# LSR_CNTRL.net
KiCad netlist of a schematic drawn in EAGLE
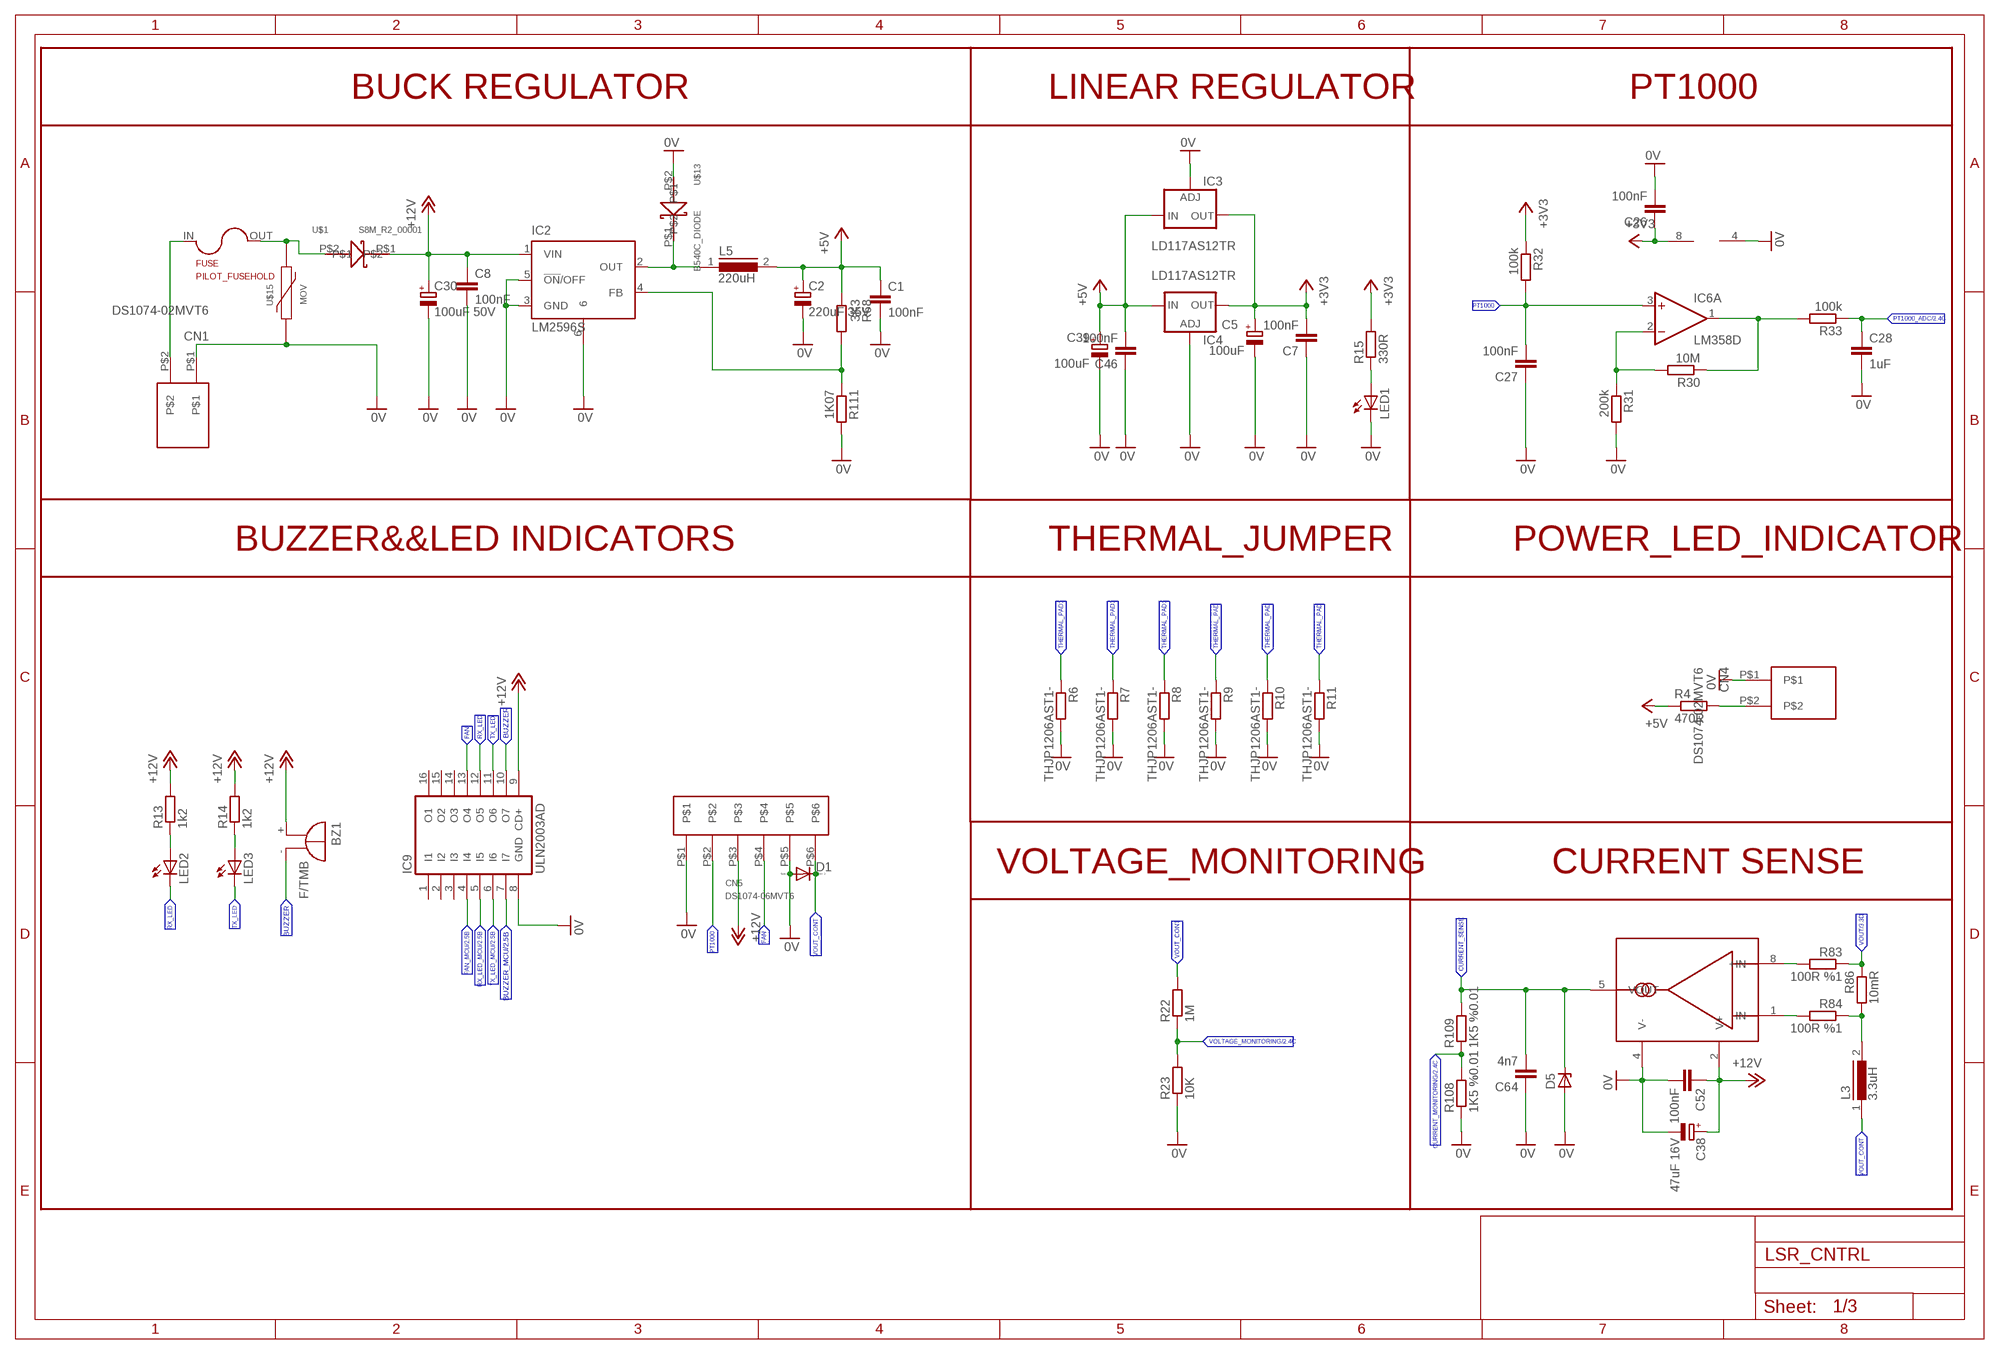
[diagram p0: schematic, sheet 1]
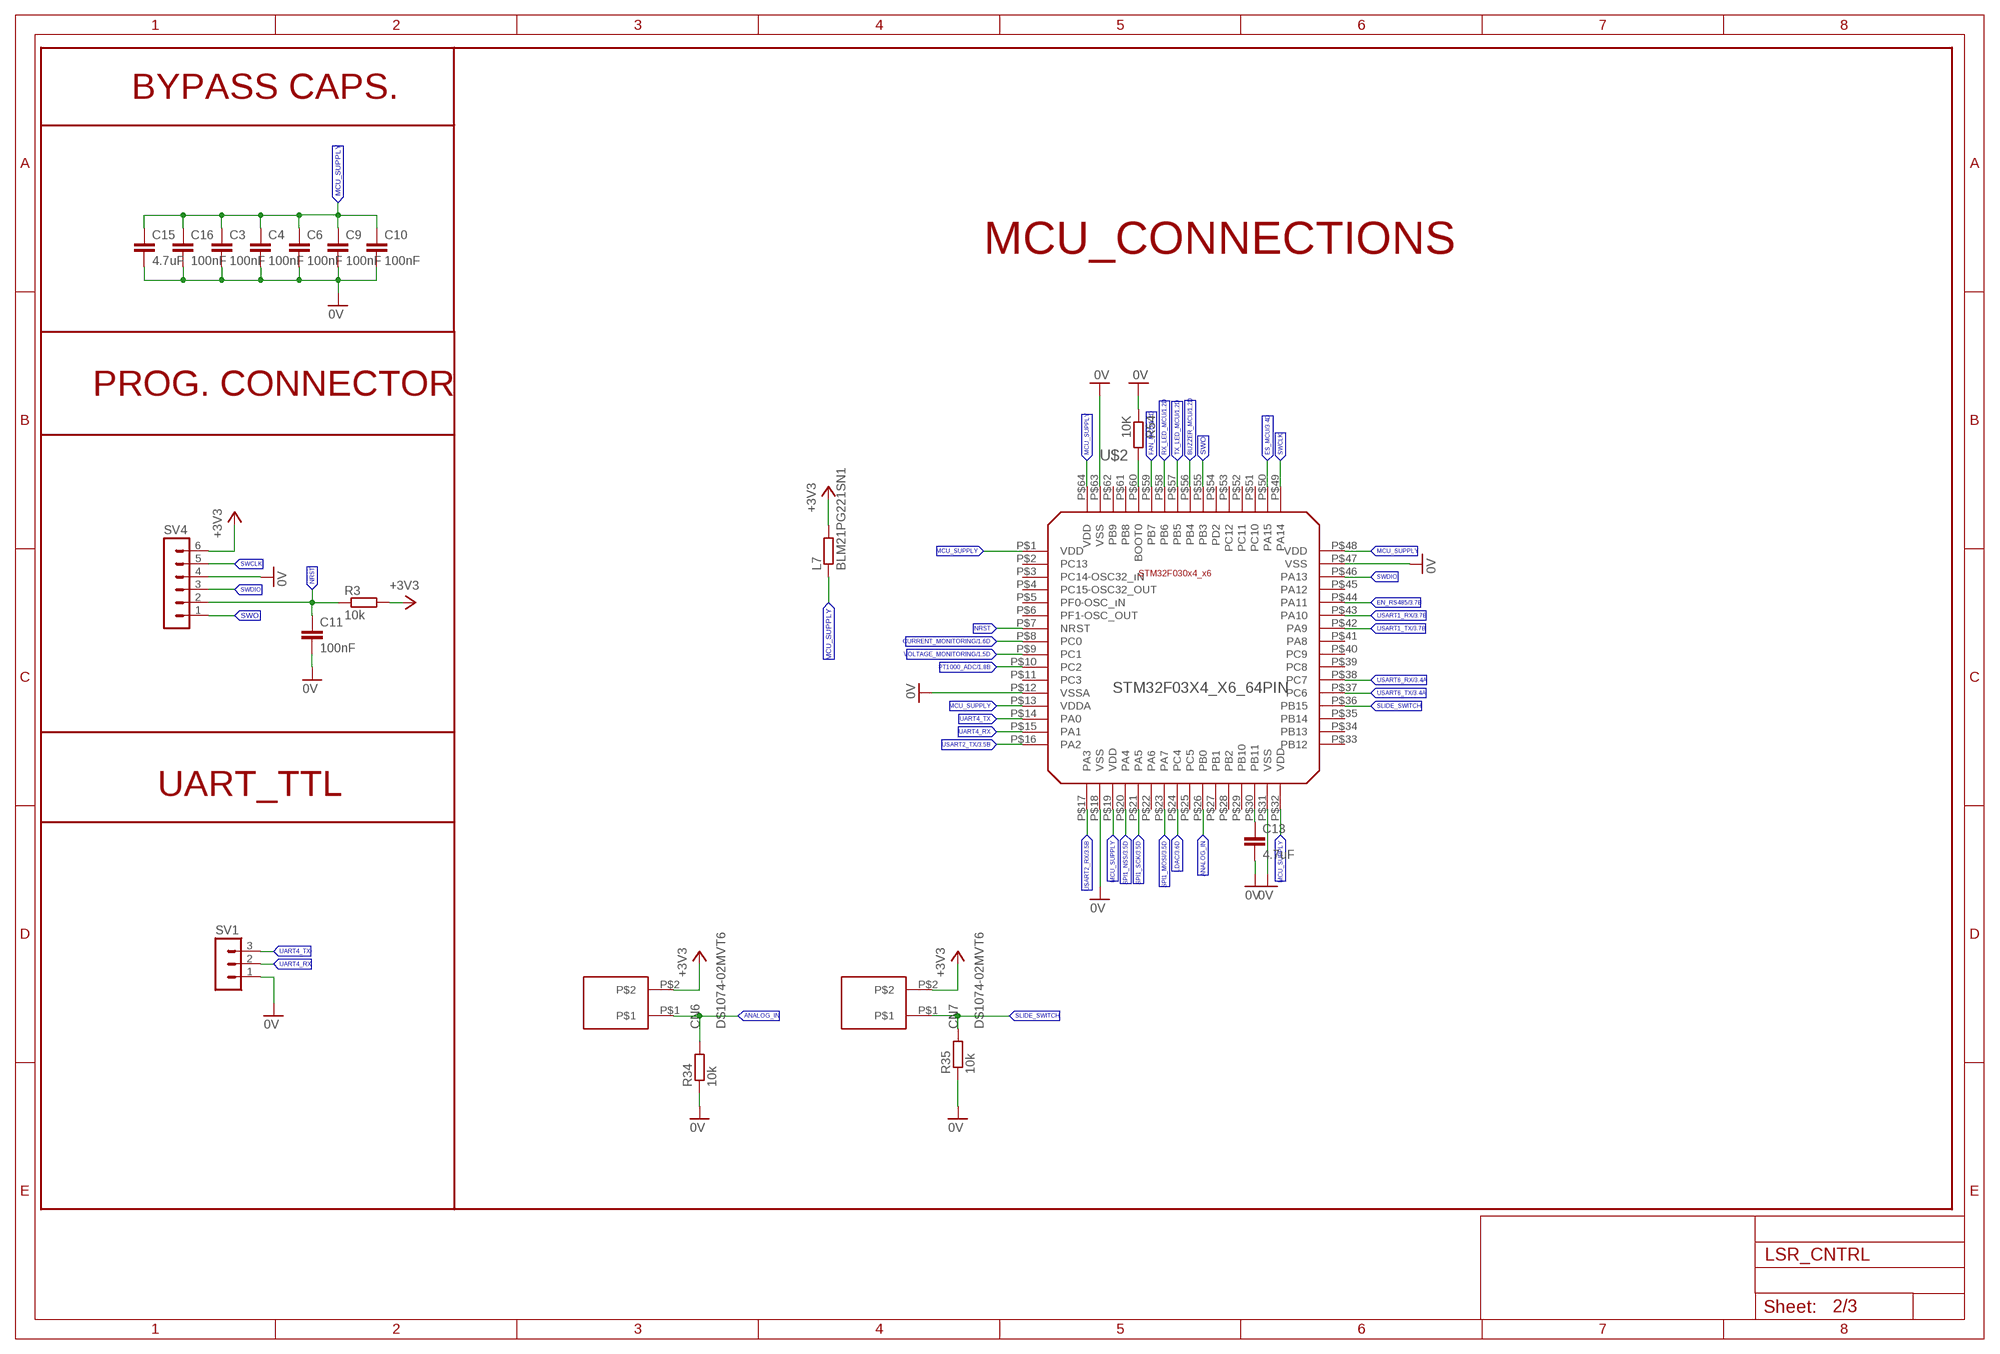
[diagram p1: schematic, sheet 2]
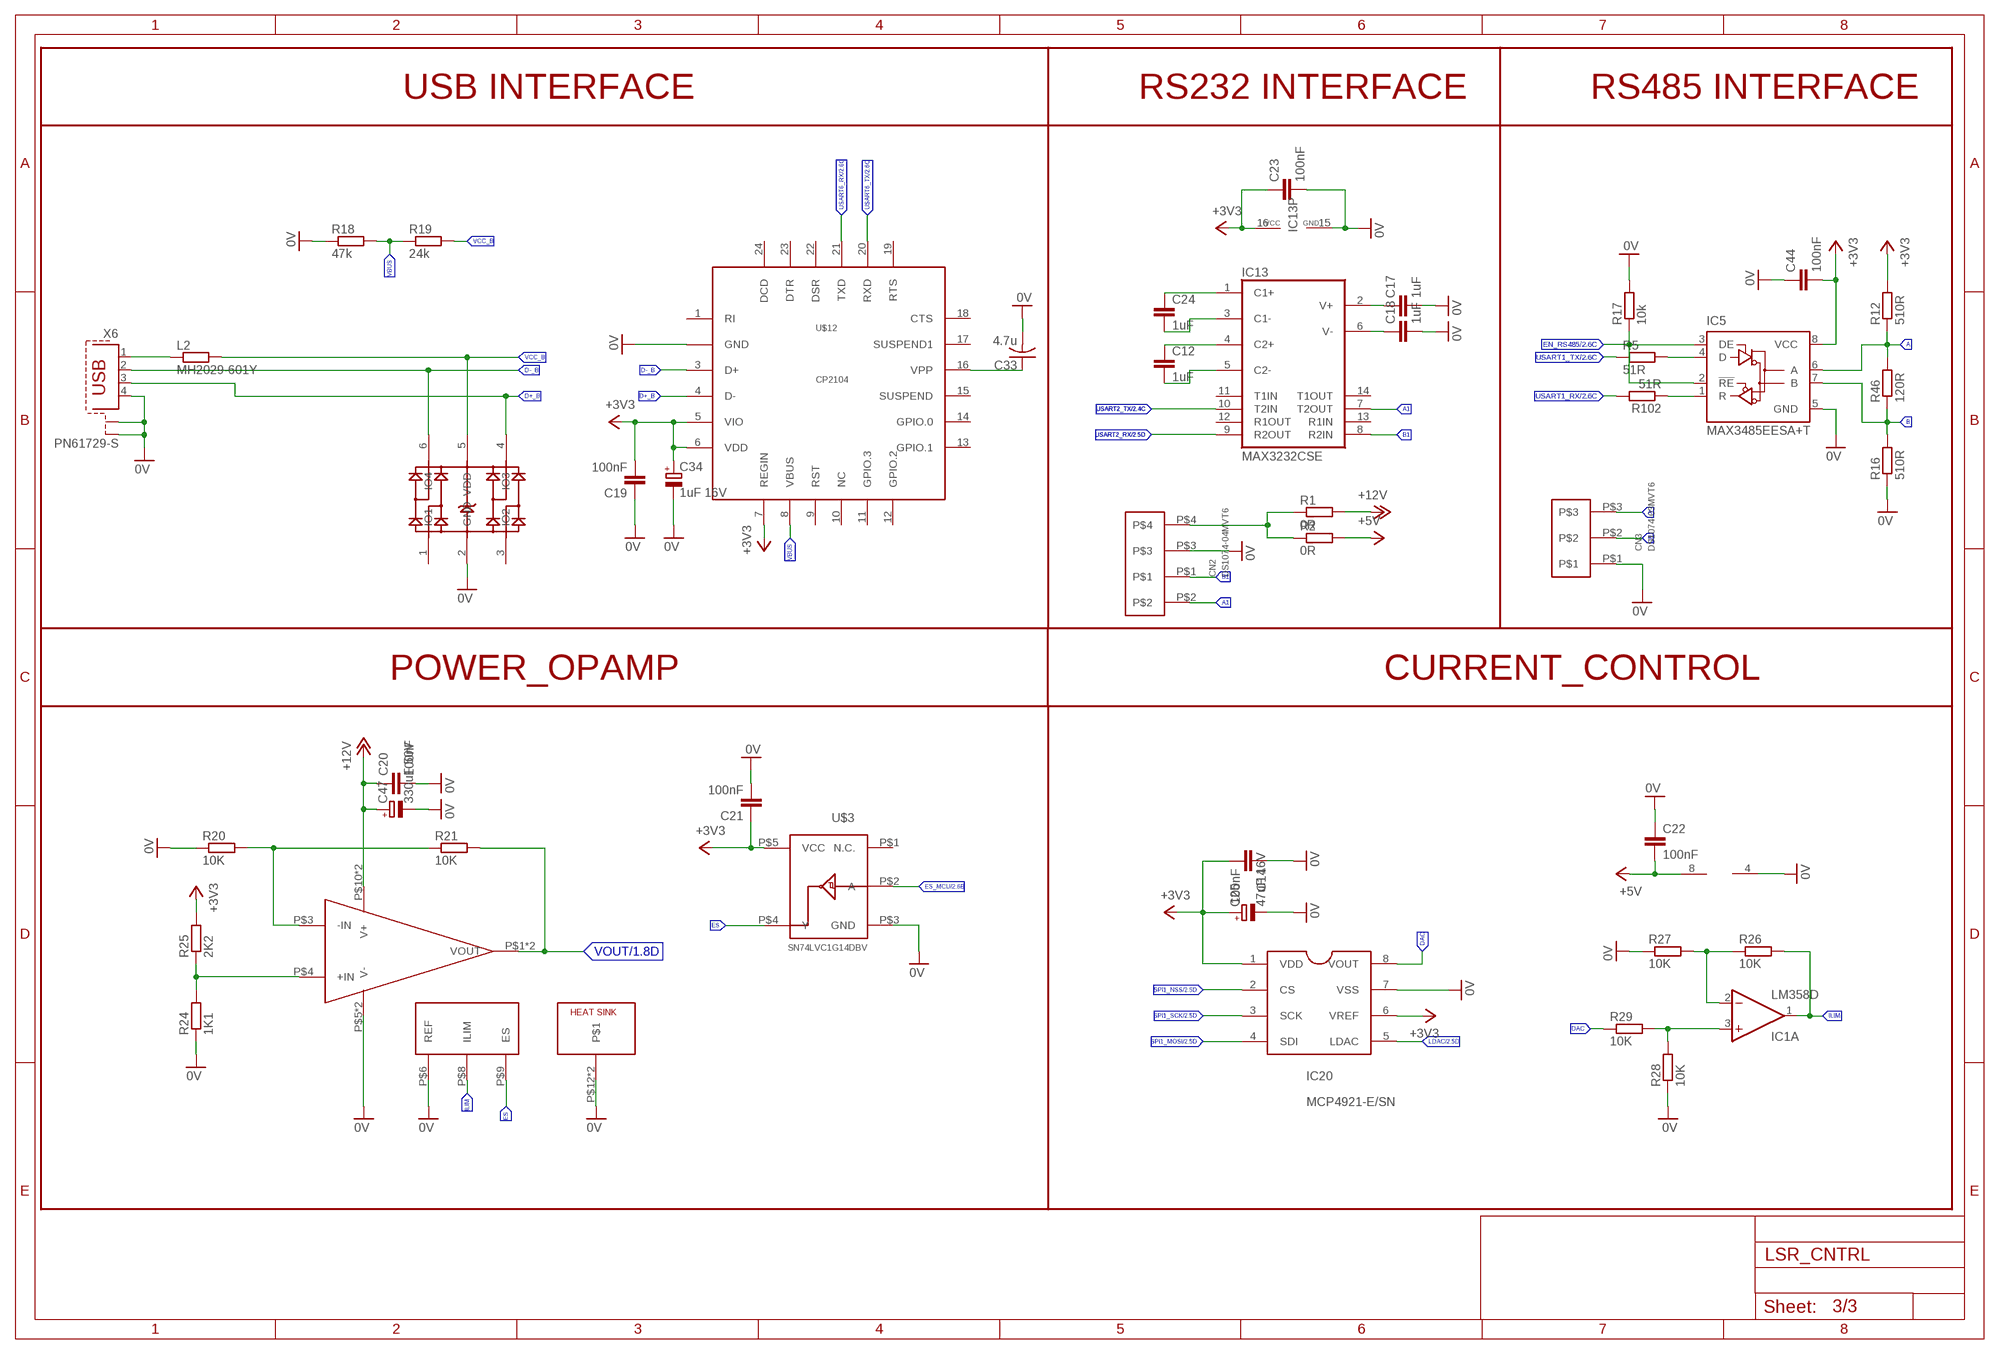
[diagram p2: schematic, sheet 3]

(export (version "E")
  (design (tool "Eeschema 10.0.6"))
  (components
    (comp (ref "C12")
      (value "1uF")
      (footprint "eagle-import:C1206")
      (libsource (lib "eagle-import") (part "C-EUC1206"))
    )
    (comp (ref "C14")
      (value "100nF")
      (footprint "eagle-import:C0603")
      (libsource (lib "eagle-import") (part "C-EUC0603"))
    )
    (comp (ref "C17")
      (value "1uF")
      (footprint "eagle-import:C1206")
      (libsource (lib "eagle-import") (part "C-EUC1206"))
    )
    (comp (ref "C18")
      (value "1uF")
      (footprint "eagle-import:C1206")
      (libsource (lib "eagle-import") (part "C-EUC1206"))
    )
    (comp (ref "C19")
      (value "100nF")
      (footprint "eagle-import:C0603")
      (libsource (lib "eagle-import") (part "C-EUC0603"))
    )
    (comp (ref "C20")
      (value "100nF")
      (footprint "eagle-import:C0603")
      (libsource (lib "eagle-import") (part "C-EUC0603"))
    )
    (comp (ref "C21")
      (value "100nF")
      (footprint "eagle-import:C0603")
      (libsource (lib "eagle-import") (part "C-EUC0603"))
    )
    (comp (ref "C22")
      (value "100nF")
      (footprint "eagle-import:C0603")
      (libsource (lib "eagle-import") (part "C-EUC0603"))
    )
    (comp (ref "C23")
      (value "100nF")
      (footprint "eagle-import:C0603")
      (libsource (lib "eagle-import") (part "C-EUC0603"))
    )
    (comp (ref "C24")
      (value "1uF")
      (footprint "eagle-import:C1206")
      (libsource (lib "eagle-import") (part "C-EUC1206"))
    )
    (comp (ref "C25")
      (value "47uF 16V")
      (footprint "eagle-import:B_3528-21R")
      (libsource (lib "eagle-import") (part "CPOL-EUB/3528-21R"))
    )
    (comp (ref "C33")
      (value "4.7u")
      (footprint "eagle-import:C0805")
      (libsource (lib "eagle-import") (part "C-USC0805"))
    )
    (comp (ref "C34")
      (value "1uF 16V")
      (footprint "eagle-import:SMC_Z")
      (libsource (lib "eagle-import") (part "CPOL-EUSMCZ"))
    )
    (comp (ref "C44")
      (value "100nF")
      (footprint "eagle-import:C0603")
      (libsource (lib "eagle-import") (part "C-EUC0603"))
    )
    (comp (ref "C47")
      (value "330uF 50V")
      (footprint "eagle-import:E5-10,5")
      (libsource (lib "eagle-import") (part "CPOL-EUE5-10.5"))
    )
    (comp (ref "CN2")
      (value "DS1074-04MVT6")
      (footprint "eagle-import:DS1074-04MVT6")
      (libsource (lib "eagle-import") (part "DS1074-04MVT6"))
    )
    (comp (ref "CN3")
      (value "DS1074-03MVT6")
      (footprint "eagle-import:DS1074-03MVT6")
      (libsource (lib "eagle-import") (part "DS1074-03MVT6"))
    )
    (comp (ref "IC1")
      (value "LM358D")
      (footprint "eagle-import:SO08")
      (libsource (lib "eagle-import") (part "LM358D"))
    )
    (comp (ref "IC5")
      (value "MAX3485EESA+T")
      (footprint "eagle-import:D_R-PDSO-G8")
      (libsource (lib "eagle-import") (part "75176AD"))
    )
    (comp (ref "IC13")
      (value "MAX3232CSE")
      (footprint "eagle-import:SO16")
      (libsource (lib "eagle-import") (part "MAX3232SEC"))
    )
    (comp (ref "IC20")
      (value "MCP4921-E/SN")
      (footprint "eagle-import:SO-08-MCP")
      (libsource (lib "eagle-import") (part "MCP4921-E/SN"))
    )
    (comp (ref "L2")
      (value "MH2029-601Y")
      (footprint "eagle-import:R0805")
      (libsource (lib "eagle-import") (part "R-EU_R0805"))
    )
    (comp (ref "OPAMP1")
      (value "OPA549MKVC")
      (footprint "eagle-import:OPA549MKVC")
      (libsource (lib "eagle-import") (part "OPA549MKVC"))
    )
    (comp (ref "R1")
      (value "0R")
      (footprint "eagle-import:R0805")
      (libsource (lib "eagle-import") (part "R-EU_R0805"))
    )
    (comp (ref "R2")
      (value "0R")
      (footprint "eagle-import:R0805")
      (libsource (lib "eagle-import") (part "R-EU_R0805"))
    )
    (comp (ref "R5")
      (value "51R")
      (footprint "eagle-import:R0603")
      (libsource (lib "eagle-import") (part "R-EU_R0603"))
    )
    (comp (ref "R12")
      (value "510R")
      (footprint "eagle-import:R0603")
      (libsource (lib "eagle-import") (part "R-EU_R0603"))
    )
    (comp (ref "R16")
      (value "510R")
      (footprint "eagle-import:R0603")
      (libsource (lib "eagle-import") (part "R-EU_R0603"))
    )
    (comp (ref "R17")
      (value "10k")
      (footprint "eagle-import:R0603")
      (libsource (lib "eagle-import") (part "R-EU_R0603"))
    )
    (comp (ref "R18")
      (value "47k")
      (footprint "eagle-import:R0805")
      (libsource (lib "eagle-import") (part "R-EU_R0805"))
    )
    (comp (ref "R19")
      (value "24k")
      (footprint "eagle-import:R0805")
      (libsource (lib "eagle-import") (part "R-EU_R0805"))
    )
    (comp (ref "R20")
      (value "10K")
      (footprint "eagle-import:R0805")
      (libsource (lib "eagle-import") (part "R-EU_R0805"))
    )
    (comp (ref "R21")
      (value "10K")
      (footprint "eagle-import:R0805")
      (libsource (lib "eagle-import") (part "R-EU_R0805"))
    )
    (comp (ref "R24")
      (value "1K1")
      (footprint "eagle-import:R0805")
      (libsource (lib "eagle-import") (part "R-EU_R0805"))
    )
    (comp (ref "R25")
      (value "2K2")
      (footprint "eagle-import:R0805")
      (libsource (lib "eagle-import") (part "R-EU_R0805"))
    )
    (comp (ref "R26")
      (value "10K")
      (footprint "eagle-import:R0805")
      (libsource (lib "eagle-import") (part "R-EU_R0805"))
    )
    (comp (ref "R27")
      (value "10K")
      (footprint "eagle-import:R0805")
      (libsource (lib "eagle-import") (part "R-EU_R0805"))
    )
    (comp (ref "R28")
      (value "10K")
      (footprint "eagle-import:R0805")
      (libsource (lib "eagle-import") (part "R-EU_R0805"))
    )
    (comp (ref "R29")
      (value "10K")
      (footprint "eagle-import:R0805")
      (libsource (lib "eagle-import") (part "R-EU_R0805"))
    )
    (comp (ref "R46")
      (value "120R")
      (footprint "eagle-import:R0603")
      (libsource (lib "eagle-import") (part "R-EU_R0603"))
    )
    (comp (ref "R102")
      (value "51R")
      (footprint "eagle-import:R0603")
      (libsource (lib "eagle-import") (part "R-EU_R0603"))
    )
    (comp (ref "TVS1")
      (value "824001")
      (footprint "eagle-import:SOT23-6")
      (libsource (lib "eagle-import") (part "824001"))
    )
    (comp (ref "U$3")
      (value "SN74LVC1G14DBV")
      (footprint "eagle-import:SOT-23-DBV")
      (libsource (lib "eagle-import") (part "SN74LVC1G14DBV"))
    )
    (comp (ref "U$12")
      (value "CP2104")
      (footprint "eagle-import:CP2104")
      (libsource (lib "eagle-import") (part "CP2104"))
    )
    (comp (ref "X6")
      (value "PN61729-S")
      (footprint "eagle-import:PN61729-S")
      (libsource (lib "eagle-import") (part "PN61729-S"))
    )
    (comp (ref "BZ1")
      (value "F/TMB")
      (footprint "eagle-import:F_TMB")
      (libsource (lib "eagle-import") (part "F/TMB"))
    )
    (comp (ref "C1")
      (value "100nF")
      (footprint "eagle-import:C0805")
      (libsource (lib "eagle-import") (part "C-EUC0805"))
    )
    (comp (ref "C2")
      (value "220uF 35V")
      (footprint "eagle-import:153CLV-0810")
      (libsource (lib "eagle-import") (part "CPOL-EU153CLV-0810"))
    )
    (comp (ref "C5")
      (value "100uF")
      (footprint "eagle-import:153CLV-0605")
      (libsource (lib "eagle-import") (part "CPOL-EU153CLV-0605"))
    )
    (comp (ref "C7")
      (value "100nF")
      (footprint "eagle-import:C0603")
      (libsource (lib "eagle-import") (part "C-EUC0603"))
    )
    (comp (ref "C8")
      (value "100nF")
      (footprint "eagle-import:C0805")
      (libsource (lib "eagle-import") (part "C-EUC0805"))
    )
    (comp (ref "C26")
      (value "100nF")
      (footprint "eagle-import:C0603")
      (libsource (lib "eagle-import") (part "C-EUC0603"))
    )
    (comp (ref "C27")
      (value "100nF")
      (footprint "eagle-import:C0603")
      (libsource (lib "eagle-import") (part "C-EUC0603"))
    )
    (comp (ref "C28")
      (value "1uF")
      (footprint "eagle-import:C1206")
      (libsource (lib "eagle-import") (part "C-EUC1206"))
    )
    (comp (ref "C30")
      (value "100uF 50V")
      (footprint "eagle-import:153CLV-0810")
      (libsource (lib "eagle-import") (part "CPOL-EU153CLV-0810"))
    )
    (comp (ref "C38")
      (value "47uF 16V")
      (footprint "eagle-import:B_3528-21R")
      (libsource (lib "eagle-import") (part "CPOL-EUB/3528-21R"))
    )
    (comp (ref "C39")
      (value "100uF")
      (footprint "eagle-import:153CLV-0605")
      (libsource (lib "eagle-import") (part "CPOL-EU153CLV-0605"))
    )
    (comp (ref "C46")
      (value "100nF")
      (footprint "eagle-import:C0603")
      (libsource (lib "eagle-import") (part "C-EUC0603"))
    )
    (comp (ref "C52")
      (value "100nF")
      (footprint "eagle-import:C0805")
      (libsource (lib "eagle-import") (part "C-EUC0805"))
    )
    (comp (ref "C64")
      (value "4n7")
      (footprint "eagle-import:C0805")
      (libsource (lib "eagle-import") (part "C-EUC0805"))
    )
    (comp (ref "CN1")
      (value "DS1074-02MVT6")
      (footprint "eagle-import:DS1074-02MVT6")
      (libsource (lib "eagle-import") (part "DS1074-02MVT6"))
    )
    (comp (ref "CN4")
      (value "DS1074-02MVT6")
      (footprint "eagle-import:DS1074-02MVT6")
      (libsource (lib "eagle-import") (part "DS1074-02MVT6"))
    )
    (comp (ref "CN5")
      (value "DS1074-06MVT6")
      (footprint "eagle-import:DS1074-06MVT6")
      (libsource (lib "eagle-import") (part "DS1074-06MVT6"))
    )
    (comp (ref "D1")
      (value "DIODE-SMB")
      (footprint "eagle-import:SMB")
      (libsource (lib "eagle-import") (part "DIODE-SMB"))
    )
    (comp (ref "D5")
      (value "ZENER-DIODESOD80C")
      (footprint "eagle-import:SOD80C")
      (libsource (lib "eagle-import") (part "ZENER-DIODESOD80C"))
    )
    (comp (ref "FUSE")
      (value "PILOT_FUSEHOLD")
      (footprint "eagle-import:RTM_FUSEHOLD")
      (libsource (lib "eagle-import") (part "RTM_FUSEHOLD"))
    )
    (comp (ref "IC2")
      (value "LM2596S")
      (footprint "eagle-import:TO263-5")
      (fields (field (name "MF") "NATIONAL SEMICONDUCTOR") (field (name "MPN") "LM2596S-ADJ/NOPB"))
      (libsource (lib "eagle-import") (part "LM2596S"))
    )
    (comp (ref "IC3")
      (value "LD117AS12TR")
      (footprint "eagle-import:SOT223")
      (libsource (lib "eagle-import") (part "LD117A?S12TR"))
    )
    (comp (ref "IC4")
      (value "LD117AS12TR")
      (footprint "eagle-import:SOT223")
      (libsource (lib "eagle-import") (part "LD117A?S12TR"))
    )
    (comp (ref "IC6")
      (value "LM358D")
      (footprint "eagle-import:SO08")
      (libsource (lib "eagle-import") (part "LM358D"))
    )
    (comp (ref "IC9")
      (value "ULN2003AD")
      (footprint "eagle-import:SO16")
      (libsource (lib "eagle-import") (part "ULN2003AD"))
    )
    (comp (ref "L3")
      (value "3.3uH")
      (footprint "eagle-import:DR127")
      (libsource (lib "eagle-import") (part "DR127"))
    )
    (comp (ref "L5")
      (value "220uH")
      (footprint "eagle-import:DR125")
      (libsource (lib "eagle-import") (part "DR125"))
    )
    (comp (ref "LED1")
      (value "LEDCHIPLED_0805")
      (footprint "eagle-import:CHIPLED_0805")
      (libsource (lib "eagle-import") (part "LEDCHIPLED_0805"))
    )
    (comp (ref "LED2")
      (value "LEDCHIPLED_0805")
      (footprint "eagle-import:CHIPLED_0805")
      (libsource (lib "eagle-import") (part "LEDCHIPLED_0805"))
    )
    (comp (ref "LED3")
      (value "LEDCHIPLED_0805")
      (footprint "eagle-import:CHIPLED_0805")
      (libsource (lib "eagle-import") (part "LEDCHIPLED_0805"))
    )
    (comp (ref "R4")
      (value "470R")
      (footprint "eagle-import:M0805")
      (libsource (lib "eagle-import") (part "R-EU_M0805"))
    )
    (comp (ref "R6")
      (value "THJP1206AST1-")
      (footprint "eagle-import:M0805")
      (libsource (lib "eagle-import") (part "R-EU_M0805"))
    )
    (comp (ref "R7")
      (value "THJP1206AST1-")
      (footprint "eagle-import:M0805")
      (libsource (lib "eagle-import") (part "R-EU_M0805"))
    )
    (comp (ref "R8")
      (value "THJP1206AST1-")
      (footprint "eagle-import:M0805")
      (libsource (lib "eagle-import") (part "R-EU_M0805"))
    )
    (comp (ref "R9")
      (value "THJP1206AST1-")
      (footprint "eagle-import:M0805")
      (libsource (lib "eagle-import") (part "R-EU_M0805"))
    )
    (comp (ref "R10")
      (value "THJP1206AST1-")
      (footprint "eagle-import:M0805")
      (libsource (lib "eagle-import") (part "R-EU_M0805"))
    )
    (comp (ref "R11")
      (value "THJP1206AST1-")
      (footprint "eagle-import:M0805")
      (libsource (lib "eagle-import") (part "R-EU_M0805"))
    )
    (comp (ref "R13")
      (value "1k2")
      (footprint "eagle-import:R0603")
      (libsource (lib "eagle-import") (part "R-EU_R0603"))
    )
    (comp (ref "R14")
      (value "1k2")
      (footprint "eagle-import:R0603")
      (libsource (lib "eagle-import") (part "R-EU_R0603"))
    )
    (comp (ref "R15")
      (value "330R")
      (footprint "eagle-import:R0603")
      (libsource (lib "eagle-import") (part "R-EU_R0603"))
    )
    (comp (ref "R22")
      (value "1M")
      (footprint "eagle-import:R0603")
      (libsource (lib "eagle-import") (part "R-EU_R0603"))
    )
    (comp (ref "R23")
      (value "10K")
      (footprint "eagle-import:R0603")
      (libsource (lib "eagle-import") (part "R-EU_R0603"))
    )
    (comp (ref "R30")
      (value "10M")
      (footprint "eagle-import:R0603")
      (libsource (lib "eagle-import") (part "R-EU_R0603"))
    )
    (comp (ref "R31")
      (value "200k")
      (footprint "eagle-import:R0603")
      (libsource (lib "eagle-import") (part "R-EU_R0603"))
    )
    (comp (ref "R32")
      (value "100k")
      (footprint "eagle-import:R0603")
      (libsource (lib "eagle-import") (part "R-EU_R0603"))
    )
    (comp (ref "R33")
      (value "100k")
      (footprint "eagle-import:R0603")
      (libsource (lib "eagle-import") (part "R-EU_R0603"))
    )
    (comp (ref "R68")
      (value "3K3")
      (footprint "eagle-import:M0805")
      (libsource (lib "eagle-import") (part "R-EU_M0805"))
    )
    (comp (ref "R83")
      (value "100R %1")
      (footprint "eagle-import:R0805")
      (libsource (lib "eagle-import") (part "R-EU_R0805"))
    )
    (comp (ref "R84")
      (value "100R %1")
      (footprint "eagle-import:R0805")
      (libsource (lib "eagle-import") (part "R-EU_R0805"))
    )
    (comp (ref "R86")
      (value "10mR")
      (footprint "eagle-import:R2512")
      (libsource (lib "eagle-import") (part "R-EU_R2512"))
    )
    (comp (ref "R108")
      (value "1K5 %0.01")
      (footprint "eagle-import:R0603")
      (libsource (lib "eagle-import") (part "R-EU_R0603"))
    )
    (comp (ref "R109")
      (value "1K5 %0.01")
      (footprint "eagle-import:R0603")
      (libsource (lib "eagle-import") (part "R-EU_R0603"))
    )
    (comp (ref "R111")
      (value "1K07")
      (footprint "eagle-import:M0805")
      (libsource (lib "eagle-import") (part "R-EU_M0805"))
    )
    (comp (ref "U$1")
      (value "S8M_R2_00001")
      (footprint "eagle-import:SMC")
      (libsource (lib "eagle-import") (part "B540C_DIODE"))
    )
    (comp (ref "U$5")
      (value "LT6105")
      (footprint "eagle-import:MSOP-8")
      (libsource (lib "eagle-import") (part "LT6105"))
    )
    (comp (ref "U$13")
      (value "B540C_DIODE")
      (footprint "eagle-import:SMC")
      (libsource (lib "eagle-import") (part "B540C_DIODE"))
    )
    (comp (ref "U$15")
      (value "MOV-10D201K")
      (footprint "eagle-import:MOV-10D201K")
      (libsource (lib "eagle-import") (part "MOV-10D201K"))
    )
    (comp (ref "C3")
      (value "100nF")
      (footprint "eagle-import:C0603")
      (libsource (lib "eagle-import") (part "C-EUC0603"))
    )
    (comp (ref "C4")
      (value "100nF")
      (footprint "eagle-import:C0603")
      (libsource (lib "eagle-import") (part "C-EUC0603"))
    )
    (comp (ref "C6")
      (value "100nF")
      (footprint "eagle-import:C0603")
      (libsource (lib "eagle-import") (part "C-EUC0603"))
    )
    (comp (ref "C9")
      (value "100nF")
      (footprint "eagle-import:C0603")
      (libsource (lib "eagle-import") (part "C-EUC0603"))
    )
    (comp (ref "C10")
      (value "100nF")
      (footprint "eagle-import:C0603")
      (libsource (lib "eagle-import") (part "C-EUC0603"))
    )
    (comp (ref "C11")
      (value "100nF")
      (footprint "eagle-import:C0603")
      (libsource (lib "eagle-import") (part "C-EUC0603"))
    )
    (comp (ref "C13")
      (value "4.7uF")
      (footprint "eagle-import:C0805")
      (libsource (lib "eagle-import") (part "C-EUC0805"))
    )
    (comp (ref "C15")
      (value "4.7uF")
      (footprint "eagle-import:C0805")
      (libsource (lib "eagle-import") (part "C-EUC0805"))
    )
    (comp (ref "C16")
      (value "100nF")
      (footprint "eagle-import:C0603")
      (libsource (lib "eagle-import") (part "C-EUC0603"))
    )
    (comp (ref "CN6")
      (value "DS1074-02MVT6")
      (footprint "eagle-import:DS1074-02MVT6")
      (libsource (lib "eagle-import") (part "DS1074-02MVT6"))
    )
    (comp (ref "CN7")
      (value "DS1074-02MVT6")
      (footprint "eagle-import:DS1074-02MVT6")
      (libsource (lib "eagle-import") (part "DS1074-02MVT6"))
    )
    (comp (ref "L7")
      (value "BLM21PG221SN1")
      (footprint "eagle-import:R0805")
      (libsource (lib "eagle-import") (part "R-EU_R0805"))
    )
    (comp (ref "R3")
      (value "10k")
      (footprint "eagle-import:R0603")
      (libsource (lib "eagle-import") (part "R-EU_R0603"))
    )
    (comp (ref "R34")
      (value "10k")
      (footprint "eagle-import:R0603")
      (libsource (lib "eagle-import") (part "R-EU_R0603"))
    )
    (comp (ref "R35")
      (value "10k")
      (footprint "eagle-import:R0603")
      (libsource (lib "eagle-import") (part "R-EU_R0603"))
    )
    (comp (ref "R54")
      (value "10K")
      (footprint "eagle-import:R0603")
      (libsource (lib "eagle-import") (part "R-EU_R0603"))
    )
    (comp (ref "SV1")
      (value "MA03-1")
      (footprint "eagle-import:MA03-1")
      (libsource (lib "eagle-import") (part "MA03-1"))
    )
    (comp (ref "SV4")
      (value "MA06-1")
      (footprint "eagle-import:MA06-1")
      (libsource (lib "eagle-import") (part "MA06-1"))
    )
    (comp (ref "U$2")
      (value "STM32F03X4_X6_64PIN")
      (footprint "eagle-import:LQFP64")
      (libsource (lib "eagle-import") (part "STM32F03X4_X6_64PIN"))
    )
  )
  (nets
    (net (code "1") (name "+3V3") (class "Default")
      (node (ref "C14") (pin "2") (pinfunction "2_2") (pintype "passive"))
      (node (ref "C19") (pin "2") (pinfunction "2_2") (pintype "passive"))
      (node (ref "C21") (pin "1") (pinfunction "1_1") (pintype "passive"))
      (node (ref "C23") (pin "1") (pinfunction "1_1") (pintype "passive"))
      (node (ref "C25") (pin "+") (pinfunction "+_+") (pintype "passive"))
      (node (ref "C26") (pin "1") (pinfunction "1_1") (pintype "passive"))
      (node (ref "C34") (pin "+") (pinfunction "+_+") (pintype "passive"))
      (node (ref "C44") (pin "2") (pinfunction "2_2") (pintype "passive"))
      (node (ref "C5") (pin "+") (pinfunction "+_+") (pintype "passive"))
      (node (ref "C7") (pin "2") (pinfunction "2_2") (pintype "passive"))
      (node (ref "CN6") (pin "P$2") (pinfunction "P$2_P$2") (pintype "bidirectional"))
      (node (ref "CN7") (pin "P$2") (pinfunction "P$2_P$2") (pintype "bidirectional"))
      (node (ref "IC13") (pin "16") (pinfunction "VCC_16") (pintype "power_in"))
      (node (ref "IC20") (pin "1") (pinfunction "VDD_1") (pintype "bidirectional"))
      (node (ref "IC20") (pin "6") (pinfunction "VREF_6") (pintype "bidirectional"))
      (node (ref "IC3") (pin "4") (pinfunction "OUT_4") (pintype "passive"))
      (node (ref "IC4") (pin "4") (pinfunction "OUT_4") (pintype "passive"))
      (node (ref "IC5") (pin "8") (pinfunction "VCC_8") (pintype "power_in"))
      (node (ref "IC6") (pin "8") (pinfunction "V+_8") (pintype "power_in"))
      (node (ref "L7") (pin "2") (pinfunction "2_2") (pintype "passive"))
      (node (ref "R12") (pin "2") (pinfunction "2_2") (pintype "passive"))
      (node (ref "R15") (pin "2") (pinfunction "2_2") (pintype "passive"))
      (node (ref "R25") (pin "2") (pinfunction "2_2") (pintype "passive"))
      (node (ref "R3") (pin "2") (pinfunction "2_2") (pintype "passive"))
      (node (ref "R32") (pin "1") (pinfunction "1_1") (pintype "passive"))
      (node (ref "SV4") (pin "6") (pinfunction "6_6") (pintype "passive"))
      (node (ref "U$12") (pin "5") (pinfunction "VIO_5") (pintype "bidirectional"))
      (node (ref "U$12") (pin "6") (pinfunction "VDD_6") (pintype "bidirectional"))
      (node (ref "U$12") (pin "7") (pinfunction "REGIN_7") (pintype "bidirectional"))
      (node (ref "U$3") (pin "P$5") (pinfunction "VCC_P$5") (pintype "bidirectional"))
    )
    (net (code "2") (name "+5V") (class "Default")
      (node (ref "C1") (pin "1") (pinfunction "1_1") (pintype "passive"))
      (node (ref "C2") (pin "+") (pinfunction "+_+") (pintype "passive"))
      (node (ref "C22") (pin "2") (pinfunction "2_2") (pintype "passive"))
      (node (ref "C39") (pin "+") (pinfunction "+_+") (pintype "passive"))
      (node (ref "C46") (pin "2") (pinfunction "2_2") (pintype "passive"))
      (node (ref "IC1") (pin "8") (pinfunction "V+_8") (pintype "power_in"))
      (node (ref "IC3") (pin "3") (pinfunction "IN_3") (pintype "input"))
      (node (ref "IC4") (pin "3") (pinfunction "IN_3") (pintype "input"))
      (node (ref "L5") (pin "2") (pinfunction "2_2") (pintype "passive"))
      (node (ref "R2") (pin "2") (pinfunction "2_2") (pintype "passive"))
      (node (ref "R4") (pin "1") (pinfunction "1_1") (pintype "passive"))
      (node (ref "R68") (pin "1") (pinfunction "1_1") (pintype "passive"))
    )
    (net (code "3") (name "+12V") (class "Default")
      (node (ref "BZ1") (pin "+") (pinfunction "+_+") (pintype "passive"))
      (node (ref "C20") (pin "1") (pinfunction "1_1") (pintype "passive"))
      (node (ref "C30") (pin "+") (pinfunction "+_+") (pintype "passive"))
      (node (ref "C38") (pin "+") (pinfunction "+_+") (pintype "passive"))
      (node (ref "C47") (pin "+") (pinfunction "+_+") (pintype "passive"))
      (node (ref "C52") (pin "1") (pinfunction "1_1") (pintype "passive"))
      (node (ref "C8") (pin "1") (pinfunction "1_1") (pintype "passive"))
      (node (ref "CN5") (pin "P$3") (pinfunction "P$3_P$3") (pintype "bidirectional"))
      (node (ref "IC2") (pin "1") (pinfunction "VIN_1") (pintype "input"))
      (node (ref "IC9") (pin "9") (pinfunction "CD+_9") (pintype "passive"))
      (node (ref "OPAMP1") (pin "P$10") (pinfunction "V+_P$10") (pintype "bidirectional"))
      (node (ref "OPAMP1") (pin "P$11") (pinfunction "V+_P$11") (pintype "bidirectional"))
      (node (ref "R1") (pin "2") (pinfunction "2_2") (pintype "passive"))
      (node (ref "R13") (pin "2") (pinfunction "2_2") (pintype "passive"))
      (node (ref "R14") (pin "2") (pinfunction "2_2") (pintype "passive"))
      (node (ref "U$1") (pin "P$1") (pinfunction "P$1_P$1") (pintype "bidirectional"))
      (node (ref "U$5") (pin "2") (pinfunction "V+_2") (pintype "bidirectional"))
    )
    (net (code "4") (name "0V") (class "Default")
      (node (ref "C1") (pin "2") (pinfunction "2_2") (pintype "passive"))
      (node (ref "C10") (pin "2") (pinfunction "2_2") (pintype "passive"))
      (node (ref "C11") (pin "2") (pinfunction "2_2") (pintype "passive"))
      (node (ref "C13") (pin "2") (pinfunction "2_2") (pintype "passive"))
      (node (ref "C14") (pin "1") (pinfunction "1_1") (pintype "passive"))
      (node (ref "C15") (pin "2") (pinfunction "2_2") (pintype "passive"))
      (node (ref "C16") (pin "2") (pinfunction "2_2") (pintype "passive"))
      (node (ref "C17") (pin "2") (pinfunction "2_2") (pintype "passive"))
      (node (ref "C18") (pin "2") (pinfunction "2_2") (pintype "passive"))
      (node (ref "C19") (pin "1") (pinfunction "1_1") (pintype "passive"))
      (node (ref "C2") (pin "-") (pinfunction "-_-") (pintype "passive"))
      (node (ref "C20") (pin "2") (pinfunction "2_2") (pintype "passive"))
      (node (ref "C21") (pin "2") (pinfunction "2_2") (pintype "passive"))
      (node (ref "C22") (pin "1") (pinfunction "1_1") (pintype "passive"))
      (node (ref "C23") (pin "2") (pinfunction "2_2") (pintype "passive"))
      (node (ref "C25") (pin "-") (pinfunction "-_-") (pintype "passive"))
      (node (ref "C26") (pin "2") (pinfunction "2_2") (pintype "passive"))
      (node (ref "C27") (pin "1") (pinfunction "1_1") (pintype "passive"))
      (node (ref "C28") (pin "2") (pinfunction "2_2") (pintype "passive"))
      (node (ref "C3") (pin "2") (pinfunction "2_2") (pintype "passive"))
      (node (ref "C30") (pin "-") (pinfunction "-_-") (pintype "passive"))
      (node (ref "C33") (pin "2") (pinfunction "2_2") (pintype "passive"))
      (node (ref "C34") (pin "-") (pinfunction "-_-") (pintype "passive"))
      (node (ref "C38") (pin "-") (pinfunction "-_-") (pintype "passive"))
      (node (ref "C39") (pin "-") (pinfunction "-_-") (pintype "passive"))
      (node (ref "C4") (pin "2") (pinfunction "2_2") (pintype "passive"))
      (node (ref "C44") (pin "1") (pinfunction "1_1") (pintype "passive"))
      (node (ref "C46") (pin "1") (pinfunction "1_1") (pintype "passive"))
      (node (ref "C47") (pin "-") (pinfunction "-_-") (pintype "passive"))
      (node (ref "C5") (pin "-") (pinfunction "-_-") (pintype "passive"))
      (node (ref "C52") (pin "2") (pinfunction "2_2") (pintype "passive"))
      (node (ref "C6") (pin "2") (pinfunction "2_2") (pintype "passive"))
      (node (ref "C64") (pin "1") (pinfunction "1_1") (pintype "passive"))
      (node (ref "C7") (pin "1") (pinfunction "1_1") (pintype "passive"))
      (node (ref "C8") (pin "2") (pinfunction "2_2") (pintype "passive"))
      (node (ref "C9") (pin "2") (pinfunction "2_2") (pintype "passive"))
      (node (ref "CN1") (pin "P$1") (pinfunction "P$1_P$1") (pintype "bidirectional"))
      (node (ref "CN2") (pin "P$3") (pinfunction "P$3_P$3") (pintype "bidirectional"))
      (node (ref "CN3") (pin "P$1") (pinfunction "P$1_P$1") (pintype "bidirectional"))
      (node (ref "CN4") (pin "P$1") (pinfunction "P$1_P$1") (pintype "bidirectional"))
      (node (ref "CN5") (pin "P$1") (pinfunction "P$1_P$1") (pintype "bidirectional"))
      (node (ref "CN5") (pin "P$5") (pinfunction "P$5_P$5") (pintype "bidirectional"))
      (node (ref "D1") (pin "A") (pinfunction "A_A") (pintype "passive"))
      (node (ref "D5") (pin "A") (pinfunction "A_A") (pintype "passive"))
      (node (ref "IC1") (pin "4") (pinfunction "V-_4") (pintype "power_in"))
      (node (ref "IC13") (pin "15") (pinfunction "GND_15") (pintype "power_in"))
      (node (ref "IC2") (pin "3") (pinfunction "GND_3") (pintype "power_in"))
      (node (ref "IC2") (pin "5") (pinfunction "~{ON}/OFF_5") (pintype "input"))
      (node (ref "IC2") (pin "6") (pinfunction "6_6") (pintype "bidirectional"))
      (node (ref "IC20") (pin "7") (pinfunction "VSS_7") (pintype "bidirectional"))
      (node (ref "IC3") (pin "1") (pinfunction "ADJ_1") (pintype "input"))
      (node (ref "IC4") (pin "1") (pinfunction "ADJ_1") (pintype "input"))
      (node (ref "IC5") (pin "5") (pinfunction "GND_5") (pintype "power_in"))
      (node (ref "IC6") (pin "4") (pinfunction "V-_4") (pintype "power_in"))
      (node (ref "IC9") (pin "8") (pinfunction "GND_8") (pintype "power_in"))
      (node (ref "LED1") (pin "C") (pinfunction "C_C") (pintype "passive"))
      (node (ref "OPAMP1") (pin "P$12") (pinfunction "P$1_P$12") (pintype "bidirectional"))
      (node (ref "OPAMP1") (pin "P$13") (pinfunction "P$1_P$13") (pintype "bidirectional"))
      (node (ref "OPAMP1") (pin "P$5") (pinfunction "V-_P$5") (pintype "bidirectional"))
      (node (ref "OPAMP1") (pin "P$6") (pinfunction "REF_P$6") (pintype "bidirectional"))
      (node (ref "OPAMP1") (pin "P$7") (pinfunction "V-_P$7") (pintype "bidirectional"))
      (node (ref "R10") (pin "2") (pinfunction "2_2") (pintype "passive"))
      (node (ref "R108") (pin "1") (pinfunction "1_1") (pintype "passive"))
      (node (ref "R11") (pin "2") (pinfunction "2_2") (pintype "passive"))
      (node (ref "R111") (pin "2") (pinfunction "2_2") (pintype "passive"))
      (node (ref "R16") (pin "1") (pinfunction "1_1") (pintype "passive"))
      (node (ref "R17") (pin "2") (pinfunction "2_2") (pintype "passive"))
      (node (ref "R18") (pin "1") (pinfunction "1_1") (pintype "passive"))
      (node (ref "R20") (pin "1") (pinfunction "1_1") (pintype "passive"))
      (node (ref "R23") (pin "1") (pinfunction "1_1") (pintype "passive"))
      (node (ref "R24") (pin "1") (pinfunction "1_1") (pintype "passive"))
      (node (ref "R27") (pin "1") (pinfunction "1_1") (pintype "passive"))
      (node (ref "R28") (pin "1") (pinfunction "1_1") (pintype "passive"))
      (node (ref "R31") (pin "2") (pinfunction "2_2") (pintype "passive"))
      (node (ref "R34") (pin "1") (pinfunction "1_1") (pintype "passive"))
      (node (ref "R35") (pin "1") (pinfunction "1_1") (pintype "passive"))
      (node (ref "R54") (pin "1") (pinfunction "1_1") (pintype "passive"))
      (node (ref "R6") (pin "2") (pinfunction "2_2") (pintype "passive"))
      (node (ref "R7") (pin "2") (pinfunction "2_2") (pintype "passive"))
      (node (ref "R8") (pin "2") (pinfunction "2_2") (pintype "passive"))
      (node (ref "R9") (pin "2") (pinfunction "2_2") (pintype "passive"))
      (node (ref "SV1") (pin "1") (pinfunction "1_1") (pintype "passive"))
      (node (ref "SV4") (pin "4") (pinfunction "4_4") (pintype "passive"))
      (node (ref "TVS1") (pin "2") (pinfunction "GND_2") (pintype "bidirectional"))
      (node (ref "U$12") (pin "2") (pinfunction "GND_2") (pintype "bidirectional"))
      (node (ref "U$12") (pin "GND1") (pinfunction "GND_GND1") (pintype "bidirectional"))
      (node (ref "U$13") (pin "P$2") (pinfunction "P$2_P$2") (pintype "bidirectional"))
      (node (ref "U$15") (pin "1") (pinfunction "1_1") (pintype "bidirectional"))
      (node (ref "U$2") (pin "P$12") (pinfunction "VSSA_P$12") (pintype "bidirectional"))
      (node (ref "U$2") (pin "P$18") (pinfunction "VSS_P$18") (pintype "bidirectional"))
      (node (ref "U$2") (pin "P$31") (pinfunction "VSS_P$31") (pintype "bidirectional"))
      (node (ref "U$2") (pin "P$47") (pinfunction "VSS_P$47") (pintype "bidirectional"))
      (node (ref "U$2") (pin "P$63") (pinfunction "VSS_P$63") (pintype "bidirectional"))
      (node (ref "U$3") (pin "P$3") (pinfunction "GND_P$3") (pintype "bidirectional"))
      (node (ref "U$5") (pin "4") (pinfunction "V-_4") (pintype "bidirectional"))
      (node (ref "X6") (pin "4") (pinfunction "4_4") (pintype "passive"))
      (node (ref "X6") (pin "S1") (pinfunction "S1_S1") (pintype "passive"))
      (node (ref "X6") (pin "S2") (pinfunction "S2_S2") (pintype "passive"))
    )
    (net (code "5") (name "A") (class "Default")
      (node (ref "CN3") (pin "P$3") (pinfunction "P$3_P$3") (pintype "bidirectional"))
      (node (ref "IC5") (pin "6") (pinfunction "A_6") (pintype "output"))
      (node (ref "R12") (pin "1") (pinfunction "1_1") (pintype "passive"))
      (node (ref "R46") (pin "2") (pinfunction "2_2") (pintype "passive"))
    )
    (net (code "6") (name "A1") (class "Default")
      (node (ref "CN2") (pin "P$2") (pinfunction "P$2_P$2") (pintype "bidirectional"))
      (node (ref "IC13") (pin "7") (pinfunction "T2OUT_7") (pintype "output"))
    )
    (net (code "7") (name "ANALOG_IN") (class "Default")
      (node (ref "CN6") (pin "P$1") (pinfunction "P$1_P$1") (pintype "bidirectional"))
      (node (ref "R34") (pin "2") (pinfunction "2_2") (pintype "passive"))
      (node (ref "U$2") (pin "P$26") (pinfunction "PB0_P$26") (pintype "bidirectional"))
    )
    (net (code "8") (name "B") (class "Default")
      (node (ref "CN3") (pin "P$2") (pinfunction "P$2_P$2") (pintype "bidirectional"))
      (node (ref "IC5") (pin "7") (pinfunction "B_7") (pintype "output"))
      (node (ref "R16") (pin "2") (pinfunction "2_2") (pintype "passive"))
      (node (ref "R46") (pin "1") (pinfunction "1_1") (pintype "passive"))
    )
    (net (code "9") (name "B1") (class "Default")
      (node (ref "CN2") (pin "P$1") (pinfunction "P$1_P$1") (pintype "bidirectional"))
      (node (ref "IC13") (pin "8") (pinfunction "R2IN_8") (pintype "input"))
    )
    (net (code "10") (name "BUZZER") (class "Default")
      (node (ref "BZ1") (pin "-") (pinfunction "-_-") (pintype "passive"))
      (node (ref "IC9") (pin "10") (pinfunction "O7_10") (pintype "open_collector"))
    )
    (net (code "11") (name "BUZZER_MCU") (class "Default")
      (node (ref "IC9") (pin "7") (pinfunction "I7_7") (pintype "input"))
      (node (ref "U$2") (pin "P$56") (pinfunction "PB4_P$56") (pintype "bidirectional"))
    )
    (net (code "12") (name "CURRENT_MONITORING") (class "Default")
      (node (ref "R108") (pin "2") (pinfunction "2_2") (pintype "passive"))
      (node (ref "R109") (pin "1") (pinfunction "1_1") (pintype "passive"))
      (node (ref "U$2") (pin "P$8") (pinfunction "PC0_P$8") (pintype "bidirectional"))
    )
    (net (code "13") (name "CURRENT_SENSE") (class "Default")
      (node (ref "C64") (pin "2") (pinfunction "2_2") (pintype "passive"))
      (node (ref "D5") (pin "C") (pinfunction "C_C") (pintype "passive"))
      (node (ref "R109") (pin "2") (pinfunction "2_2") (pintype "passive"))
      (node (ref "U$5") (pin "5") (pinfunction "VOUT_5") (pintype "bidirectional"))
    )
    (net (code "14") (name "D+_B") (class "Default")
      (node (ref "TVS1") (pin "4") (pinfunction "IO3_4") (pintype "bidirectional"))
      (node (ref "U$12") (pin "4") (pinfunction "D-_4") (pintype "bidirectional"))
      (node (ref "X6") (pin "3") (pinfunction "3_3") (pintype "passive"))
    )
    (net (code "15") (name "D-_B") (class "Default")
      (node (ref "TVS1") (pin "6") (pinfunction "IO4_6") (pintype "bidirectional"))
      (node (ref "U$12") (pin "3") (pinfunction "D+_3") (pintype "bidirectional"))
      (node (ref "X6") (pin "2") (pinfunction "2_2") (pintype "passive"))
    )
    (net (code "16") (name "DAC") (class "Default")
      (node (ref "IC20") (pin "8") (pinfunction "VOUT_8") (pintype "bidirectional"))
      (node (ref "R29") (pin "1") (pinfunction "1_1") (pintype "passive"))
    )
    (net (code "17") (name "EN_RS485") (class "Default")
      (node (ref "IC5") (pin "2") (pinfunction "~{RE}_2") (pintype "input"))
      (node (ref "IC5") (pin "3") (pinfunction "DE_3") (pintype "input"))
      (node (ref "R17") (pin "1") (pinfunction "1_1") (pintype "passive"))
      (node (ref "U$2") (pin "P$44") (pinfunction "PA11_P$44") (pintype "bidirectional"))
    )
    (net (code "18") (name "ES") (class "Default")
      (node (ref "OPAMP1") (pin "P$9") (pinfunction "ES_P$9") (pintype "bidirectional"))
      (node (ref "U$3") (pin "P$4") (pinfunction "Y_P$4") (pintype "bidirectional"))
    )
    (net (code "19") (name "ES_MCU") (class "Default")
      (node (ref "U$2") (pin "P$50") (pinfunction "PA15_P$50") (pintype "bidirectional"))
      (node (ref "U$3") (pin "P$2") (pinfunction "A_P$2") (pintype "bidirectional"))
    )
    (net (code "20") (name "FAN") (class "Default")
      (node (ref "CN5") (pin "P$4") (pinfunction "P$4_P$4") (pintype "bidirectional"))
      (node (ref "IC9") (pin "13") (pinfunction "O4_13") (pintype "open_collector"))
    )
    (net (code "21") (name "FAN_MCU") (class "Default")
      (node (ref "IC9") (pin "4") (pinfunction "I4_4") (pintype "input"))
      (node (ref "U$2") (pin "P$59") (pinfunction "PB7_P$59") (pintype "bidirectional"))
    )
    (net (code "22") (name "ILIM") (class "Default")
      (node (ref "IC1") (pin "1") (pinfunction "OUT_1") (pintype "output"))
      (node (ref "OPAMP1") (pin "P$8") (pinfunction "ILIM_P$8") (pintype "bidirectional"))
      (node (ref "R26") (pin "2") (pinfunction "2_2") (pintype "passive"))
    )
    (net (code "23") (name "LDAC") (class "Default")
      (node (ref "IC20") (pin "5") (pinfunction "LDAC_5") (pintype "bidirectional"))
      (node (ref "U$2") (pin "P$24") (pinfunction "PC4_P$24") (pintype "bidirectional"))
    )
    (net (code "24") (name "MCU_SUPPLY") (class "Default")
      (node (ref "C10") (pin "1") (pinfunction "1_1") (pintype "passive"))
      (node (ref "C15") (pin "1") (pinfunction "1_1") (pintype "passive"))
      (node (ref "C16") (pin "1") (pinfunction "1_1") (pintype "passive"))
      (node (ref "C3") (pin "1") (pinfunction "1_1") (pintype "passive"))
      (node (ref "C4") (pin "1") (pinfunction "1_1") (pintype "passive"))
      (node (ref "C6") (pin "1") (pinfunction "1_1") (pintype "passive"))
      (node (ref "C9") (pin "1") (pinfunction "1_1") (pintype "passive"))
      (node (ref "L7") (pin "1") (pinfunction "1_1") (pintype "passive"))
      (node (ref "U$2") (pin "P$1") (pinfunction "VDD_P$1") (pintype "bidirectional"))
      (node (ref "U$2") (pin "P$13") (pinfunction "VDDA_P$13") (pintype "bidirectional"))
      (node (ref "U$2") (pin "P$19") (pinfunction "VDD_P$19") (pintype "bidirectional"))
      (node (ref "U$2") (pin "P$32") (pinfunction "VDD_P$32") (pintype "bidirectional"))
      (node (ref "U$2") (pin "P$48") (pinfunction "VDD_P$48") (pintype "bidirectional"))
      (node (ref "U$2") (pin "P$64") (pinfunction "VDD_P$64") (pintype "bidirectional"))
    )
    (net (code "25") (name "NRST") (class "Default")
      (node (ref "C11") (pin "1") (pinfunction "1_1") (pintype "passive"))
      (node (ref "R3") (pin "1") (pinfunction "1_1") (pintype "passive"))
      (node (ref "SV4") (pin "2") (pinfunction "2_2") (pintype "passive"))
      (node (ref "U$2") (pin "P$7") (pinfunction "NRST_P$7") (pintype "bidirectional"))
    )
    (net (code "26") (name "Net-(CN1-PadP$2)") (class "Default")
      (node (ref "CN1") (pin "P$2") (pinfunction "P$2_P$2") (pintype "bidirectional"))
      (node (ref "FUSE") (pin "IN") (pinfunction "IN_IN") (pintype "bidirectional"))
    )
    (net (code "27") (name "Net-(CN2-PadP$4)") (class "Default")
      (node (ref "CN2") (pin "P$4") (pinfunction "P$4_P$4") (pintype "bidirectional"))
      (node (ref "R1") (pin "1") (pinfunction "1_1") (pintype "passive"))
      (node (ref "R2") (pin "1") (pinfunction "1_1") (pintype "passive"))
    )
    (net (code "28") (name "Net-(CN4-PadP$2)") (class "Default")
      (node (ref "CN4") (pin "P$2") (pinfunction "P$2_P$2") (pintype "bidirectional"))
      (node (ref "R4") (pin "2") (pinfunction "2_2") (pintype "passive"))
    )
    (net (code "29") (name "Net-(FUSE-PadOUT)") (class "Default")
      (node (ref "FUSE") (pin "OUT") (pinfunction "OUT_OUT") (pintype "bidirectional"))
      (node (ref "U$1") (pin "P$2") (pinfunction "P$2_P$2") (pintype "bidirectional"))
      (node (ref "U$15") (pin "2") (pinfunction "2_2") (pintype "bidirectional"))
    )
    (net (code "30") (name "Net-(IC1A-+IN)") (class "Default")
      (node (ref "IC1") (pin "3") (pinfunction "+IN_3") (pintype "input"))
      (node (ref "R28") (pin "2") (pinfunction "2_2") (pintype "passive"))
      (node (ref "R29") (pin "2") (pinfunction "2_2") (pintype "passive"))
    )
    (net (code "31") (name "Net-(IC1A--IN)") (class "Default")
      (node (ref "IC1") (pin "2") (pinfunction "-IN_2") (pintype "input"))
      (node (ref "R26") (pin "1") (pinfunction "1_1") (pintype "passive"))
      (node (ref "R27") (pin "2") (pinfunction "2_2") (pintype "passive"))
    )
    (net (code "32") (name "Net-(IC2-FB)") (class "Default")
      (node (ref "IC2") (pin "4") (pinfunction "FB_4") (pintype "input"))
      (node (ref "R111") (pin "1") (pinfunction "1_1") (pintype "passive"))
      (node (ref "R68") (pin "2") (pinfunction "2_2") (pintype "passive"))
    )
    (net (code "33") (name "Net-(IC2-OUT)") (class "Default")
      (node (ref "IC2") (pin "2") (pinfunction "OUT_2") (pintype "output"))
      (node (ref "L5") (pin "1") (pinfunction "1_1") (pintype "passive"))
      (node (ref "U$13") (pin "P$1") (pinfunction "P$1_P$1") (pintype "bidirectional"))
    )
    (net (code "34") (name "Net-(IC5-D)") (class "Default")
      (node (ref "IC5") (pin "4") (pinfunction "D_4") (pintype "input"))
      (node (ref "R5") (pin "2") (pinfunction "2_2") (pintype "passive"))
    )
    (net (code "35") (name "Net-(IC5-R)") (class "Default")
      (node (ref "IC5") (pin "1") (pinfunction "R_1") (pintype "input"))
      (node (ref "R102") (pin "1") (pinfunction "1_1") (pintype "passive"))
    )
    (net (code "36") (name "Net-(IC6A--IN)") (class "Default")
      (node (ref "IC6") (pin "2") (pinfunction "-IN_2") (pintype "input"))
      (node (ref "R30") (pin "2") (pinfunction "2_2") (pintype "passive"))
      (node (ref "R31") (pin "1") (pinfunction "1_1") (pintype "passive"))
    )
    (net (code "37") (name "Net-(IC6A-OUT)") (class "Default")
      (node (ref "IC6") (pin "1") (pinfunction "OUT_1") (pintype "output"))
      (node (ref "R30") (pin "1") (pinfunction "1_1") (pintype "passive"))
      (node (ref "R33") (pin "2") (pinfunction "2_2") (pintype "passive"))
    )
    (net (code "38") (name "Net-(IC13A-C1+)") (class "Default")
      (node (ref "C24") (pin "1") (pinfunction "1_1") (pintype "passive"))
      (node (ref "IC13") (pin "1") (pinfunction "C1+_1") (pintype "bidirectional"))
    )
    (net (code "39") (name "Net-(IC13A-C1-)") (class "Default")
      (node (ref "C24") (pin "2") (pinfunction "2_2") (pintype "passive"))
      (node (ref "IC13") (pin "3") (pinfunction "C1-_3") (pintype "bidirectional"))
    )
    (net (code "40") (name "Net-(IC13A-C2+)") (class "Default")
      (node (ref "C12") (pin "1") (pinfunction "1_1") (pintype "passive"))
      (node (ref "IC13") (pin "4") (pinfunction "C2+_4") (pintype "bidirectional"))
    )
    (net (code "41") (name "Net-(IC13A-C2-)") (class "Default")
      (node (ref "C12") (pin "2") (pinfunction "2_2") (pintype "passive"))
      (node (ref "IC13") (pin "5") (pinfunction "C2-_5") (pintype "bidirectional"))
    )
    (net (code "42") (name "Net-(IC13A-V+)") (class "Default")
      (node (ref "C17") (pin "1") (pinfunction "1_1") (pintype "passive"))
      (node (ref "IC13") (pin "2") (pinfunction "V+_2") (pintype "bidirectional"))
    )
    (net (code "43") (name "Net-(IC13A-V-)") (class "Default")
      (node (ref "C18") (pin "1") (pinfunction "1_1") (pintype "passive"))
      (node (ref "IC13") (pin "6") (pinfunction "V-_6") (pintype "bidirectional"))
    )
    (net (code "44") (name "Net-(L2-Pad1)") (class "Default")
      (node (ref "L2") (pin "1") (pinfunction "1_1") (pintype "passive"))
      (node (ref "X6") (pin "1") (pinfunction "1_1") (pintype "passive"))
    )
    (net (code "45") (name "Net-(L3-Pad2)") (class "Default")
      (node (ref "L3") (pin "2") (pinfunction "2_2") (pintype "passive"))
      (node (ref "R84") (pin "1") (pinfunction "1_1") (pintype "passive"))
      (node (ref "R86") (pin "2") (pinfunction "2_2") (pintype "passive"))
    )
    (net (code "46") (name "Net-(LED1-PadA)") (class "Default")
      (node (ref "LED1") (pin "A") (pinfunction "A_A") (pintype "passive"))
      (node (ref "R15") (pin "1") (pinfunction "1_1") (pintype "passive"))
    )
    (net (code "47") (name "Net-(LED2-PadA)") (class "Default")
      (node (ref "LED2") (pin "A") (pinfunction "A_A") (pintype "passive"))
      (node (ref "R13") (pin "1") (pinfunction "1_1") (pintype "passive"))
    )
    (net (code "48") (name "Net-(LED3-PadA)") (class "Default")
      (node (ref "LED3") (pin "A") (pinfunction "A_A") (pintype "passive"))
      (node (ref "R14") (pin "1") (pinfunction "1_1") (pintype "passive"))
    )
    (net (code "49") (name "Net-(OPAMP1-+IN)") (class "Default")
      (node (ref "OPAMP1") (pin "P$4") (pinfunction "+IN_P$4") (pintype "bidirectional"))
      (node (ref "R24") (pin "2") (pinfunction "2_2") (pintype "passive"))
      (node (ref "R25") (pin "1") (pinfunction "1_1") (pintype "passive"))
    )
    (net (code "50") (name "Net-(OPAMP1--IN)") (class "Default")
      (node (ref "OPAMP1") (pin "P$3") (pinfunction "-IN_P$3") (pintype "bidirectional"))
      (node (ref "R20") (pin "2") (pinfunction "2_2") (pintype "passive"))
      (node (ref "R21") (pin "1") (pinfunction "1_1") (pintype "passive"))
    )
    (net (code "51") (name "Net-(U$2-BOOT0)") (class "Default")
      (node (ref "R54") (pin "2") (pinfunction "2_2") (pintype "passive"))
      (node (ref "U$2") (pin "P$60") (pinfunction "BOOT0_P$60") (pintype "bidirectional"))
    )
    (net (code "52") (name "Net-(U$2-PB11)") (class "Default")
      (node (ref "C13") (pin "1") (pinfunction "1_1") (pintype "passive"))
      (node (ref "U$2") (pin "P$30") (pinfunction "PB11_P$30") (pintype "bidirectional"))
    )
    (net (code "53") (name "Net-(U$5-+IN)") (class "Default")
      (node (ref "R83") (pin "2") (pinfunction "2_2") (pintype "passive"))
      (node (ref "U$5") (pin "8") (pinfunction "+IN_8") (pintype "bidirectional"))
    )
    (net (code "54") (name "Net-(U$5--IN)") (class "Default")
      (node (ref "R84") (pin "2") (pinfunction "2_2") (pintype "passive"))
      (node (ref "U$5") (pin "1") (pinfunction "-IN_1") (pintype "bidirectional"))
    )
    (net (code "55") (name "Net-(U$12-VPP)") (class "Default")
      (node (ref "C33") (pin "1") (pinfunction "1_1") (pintype "passive"))
      (node (ref "U$12") (pin "16") (pinfunction "VPP_16") (pintype "bidirectional"))
    )
    (net (code "56") (name "PT1000") (class "Default")
      (node (ref "C27") (pin "2") (pinfunction "2_2") (pintype "passive"))
      (node (ref "CN5") (pin "P$2") (pinfunction "P$2_P$2") (pintype "bidirectional"))
      (node (ref "IC6") (pin "3") (pinfunction "+IN_3") (pintype "input"))
      (node (ref "R32") (pin "2") (pinfunction "2_2") (pintype "passive"))
    )
    (net (code "57") (name "PT1000_ADC") (class "Default")
      (node (ref "C28") (pin "1") (pinfunction "1_1") (pintype "passive"))
      (node (ref "R33") (pin "1") (pinfunction "1_1") (pintype "passive"))
      (node (ref "U$2") (pin "P$10") (pinfunction "PC2_P$10") (pintype "bidirectional"))
    )
    (net (code "58") (name "RX_LED") (class "Default")
      (node (ref "IC9") (pin "12") (pinfunction "O5_12") (pintype "open_collector"))
      (node (ref "LED2") (pin "C") (pinfunction "C_C") (pintype "passive"))
    )
    (net (code "59") (name "RX_LED_MCU") (class "Default")
      (node (ref "IC9") (pin "5") (pinfunction "I5_5") (pintype "input"))
      (node (ref "U$2") (pin "P$58") (pinfunction "PB6_P$58") (pintype "bidirectional"))
    )
    (net (code "60") (name "SLIDE_SWITCH") (class "Default")
      (node (ref "CN7") (pin "P$1") (pinfunction "P$1_P$1") (pintype "bidirectional"))
      (node (ref "R35") (pin "2") (pinfunction "2_2") (pintype "passive"))
      (node (ref "U$2") (pin "P$36") (pinfunction "PB15_P$36") (pintype "bidirectional"))
    )
    (net (code "61") (name "SPI1_MOSI") (class "Default")
      (node (ref "IC20") (pin "4") (pinfunction "SDI_4") (pintype "bidirectional"))
      (node (ref "U$2") (pin "P$23") (pinfunction "PA7_P$23") (pintype "bidirectional"))
    )
    (net (code "62") (name "SPI1_NSS") (class "Default")
      (node (ref "IC20") (pin "2") (pinfunction "CS_2") (pintype "bidirectional"))
      (node (ref "U$2") (pin "P$20") (pinfunction "PA4_P$20") (pintype "bidirectional"))
    )
    (net (code "63") (name "SPI1_SCK") (class "Default")
      (node (ref "IC20") (pin "3") (pinfunction "SCK_3") (pintype "bidirectional"))
      (node (ref "U$2") (pin "P$21") (pinfunction "PA5_P$21") (pintype "bidirectional"))
    )
    (net (code "64") (name "SWCLK") (class "Default")
      (node (ref "SV4") (pin "5") (pinfunction "5_5") (pintype "passive"))
      (node (ref "U$2") (pin "P$49") (pinfunction "PA14_P$49") (pintype "bidirectional"))
    )
    (net (code "65") (name "SWDIO") (class "Default")
      (node (ref "SV4") (pin "3") (pinfunction "3_3") (pintype "passive"))
      (node (ref "U$2") (pin "P$46") (pinfunction "PA13_P$46") (pintype "bidirectional"))
    )
    (net (code "66") (name "SWO") (class "Default")
      (node (ref "SV4") (pin "1") (pinfunction "1_1") (pintype "passive"))
      (node (ref "U$2") (pin "P$55") (pinfunction "PB3_P$55") (pintype "bidirectional"))
    )
    (net (code "67") (name "THERMAL_PAD") (class "Default")
      (node (ref "R10") (pin "1") (pinfunction "1_1") (pintype "passive"))
      (node (ref "R11") (pin "1") (pinfunction "1_1") (pintype "passive"))
      (node (ref "R9") (pin "1") (pinfunction "1_1") (pintype "passive"))
    )
    (net (code "68") (name "THERMAL_PAD1") (class "Default")
      (node (ref "R6") (pin "1") (pinfunction "1_1") (pintype "passive"))
      (node (ref "R7") (pin "1") (pinfunction "1_1") (pintype "passive"))
      (node (ref "R8") (pin "1") (pinfunction "1_1") (pintype "passive"))
    )
    (net (code "69") (name "TX_LED") (class "Default")
      (node (ref "IC9") (pin "11") (pinfunction "O6_11") (pintype "open_collector"))
      (node (ref "LED3") (pin "C") (pinfunction "C_C") (pintype "passive"))
    )
    (net (code "70") (name "TX_LED_MCU") (class "Default")
      (node (ref "IC9") (pin "6") (pinfunction "I6_6") (pintype "input"))
      (node (ref "U$2") (pin "P$57") (pinfunction "PB5_P$57") (pintype "bidirectional"))
    )
    (net (code "71") (name "UART4_RX") (class "Default")
      (node (ref "SV1") (pin "2") (pinfunction "2_2") (pintype "passive"))
      (node (ref "U$2") (pin "P$15") (pinfunction "PA1_P$15") (pintype "bidirectional"))
    )
    (net (code "72") (name "UART4_TX") (class "Default")
      (node (ref "SV1") (pin "3") (pinfunction "3_3") (pintype "passive"))
      (node (ref "U$2") (pin "P$14") (pinfunction "PA0_P$14") (pintype "bidirectional"))
    )
    (net (code "73") (name "USART1_RX") (class "Default")
      (node (ref "R102") (pin "2") (pinfunction "2_2") (pintype "passive"))
      (node (ref "U$2") (pin "P$43") (pinfunction "PA10_P$43") (pintype "bidirectional"))
    )
    (net (code "74") (name "USART1_TX") (class "Default")
      (node (ref "R5") (pin "1") (pinfunction "1_1") (pintype "passive"))
      (node (ref "U$2") (pin "P$42") (pinfunction "PA9_P$42") (pintype "bidirectional"))
    )
    (net (code "75") (name "USART2_RX") (class "Default")
      (node (ref "IC13") (pin "9") (pinfunction "R2OUT_9") (pintype "output"))
      (node (ref "U$2") (pin "P$17") (pinfunction "PA3_P$17") (pintype "bidirectional"))
    )
    (net (code "76") (name "USART2_TX") (class "Default")
      (node (ref "IC13") (pin "10") (pinfunction "T2IN_10") (pintype "input"))
      (node (ref "U$2") (pin "P$16") (pinfunction "PA2_P$16") (pintype "bidirectional"))
    )
    (net (code "77") (name "USART6_RX") (class "Default")
      (node (ref "U$12") (pin "21") (pinfunction "TXD_21") (pintype "bidirectional"))
      (node (ref "U$2") (pin "P$38") (pinfunction "PC7_P$38") (pintype "bidirectional"))
    )
    (net (code "78") (name "USART6_TX") (class "Default")
      (node (ref "U$12") (pin "20") (pinfunction "RXD_20") (pintype "bidirectional"))
      (node (ref "U$2") (pin "P$37") (pinfunction "PC6_P$37") (pintype "bidirectional"))
    )
    (net (code "79") (name "VBUS") (class "Default")
      (node (ref "R18") (pin "2") (pinfunction "2_2") (pintype "passive"))
      (node (ref "R19") (pin "1") (pinfunction "1_1") (pintype "passive"))
      (node (ref "U$12") (pin "8") (pinfunction "VBUS_8") (pintype "bidirectional"))
    )
    (net (code "80") (name "VCC_B") (class "Default")
      (node (ref "L2") (pin "2") (pinfunction "2_2") (pintype "passive"))
      (node (ref "R19") (pin "2") (pinfunction "2_2") (pintype "passive"))
      (node (ref "TVS1") (pin "5") (pinfunction "VDD_5") (pintype "bidirectional"))
    )
    (net (code "81") (name "VOLTAGE_MONITORING") (class "Default")
      (node (ref "R22") (pin "1") (pinfunction "1_1") (pintype "passive"))
      (node (ref "R23") (pin "2") (pinfunction "2_2") (pintype "passive"))
      (node (ref "U$2") (pin "P$9") (pinfunction "PC1_P$9") (pintype "bidirectional"))
    )
    (net (code "82") (name "VOUT") (class "Default")
      (node (ref "OPAMP1") (pin "P$1") (pinfunction "VOUT_P$1") (pintype "bidirectional"))
      (node (ref "OPAMP1") (pin "P$2") (pinfunction "VOUT_P$2") (pintype "bidirectional"))
      (node (ref "R21") (pin "2") (pinfunction "2_2") (pintype "passive"))
      (node (ref "R83") (pin "1") (pinfunction "1_1") (pintype "passive"))
      (node (ref "R86") (pin "1") (pinfunction "1_1") (pintype "passive"))
    )
    (net (code "83") (name "VOUT_CONT") (class "Default")
      (node (ref "CN5") (pin "P$6") (pinfunction "P$6_P$6") (pintype "bidirectional"))
      (node (ref "D1") (pin "C") (pinfunction "C_C") (pintype "passive"))
      (node (ref "L3") (pin "1") (pinfunction "1_1") (pintype "passive"))
      (node (ref "R22") (pin "2") (pinfunction "2_2") (pintype "passive"))
    )
    (net (code "84") (name "unconnected-(IC9-I1-Pad1)") (class "Default")
      (node (ref "IC9") (pin "1") (pinfunction "I1_1") (pintype "input"))
    )
    (net (code "85") (name "unconnected-(IC9-I2-Pad2)") (class "Default")
      (node (ref "IC9") (pin "2") (pinfunction "I2_2") (pintype "input"))
    )
    (net (code "86") (name "unconnected-(IC9-I3-Pad3)") (class "Default")
      (node (ref "IC9") (pin "3") (pinfunction "I3_3") (pintype "input"))
    )
    (net (code "87") (name "unconnected-(IC9-O1-Pad16)") (class "Default")
      (node (ref "IC9") (pin "16") (pinfunction "O1_16") (pintype "open_collector"))
    )
    (net (code "88") (name "unconnected-(IC9-O2-Pad15)") (class "Default")
      (node (ref "IC9") (pin "15") (pinfunction "O2_15") (pintype "open_collector"))
    )
    (net (code "89") (name "unconnected-(IC9-O3-Pad14)") (class "Default")
      (node (ref "IC9") (pin "14") (pinfunction "O3_14") (pintype "open_collector"))
    )
    (net (code "90") (name "unconnected-(IC13A-R1IN-Pad13)") (class "Default")
      (node (ref "IC13") (pin "13") (pinfunction "R1IN_13") (pintype "input"))
    )
    (net (code "91") (name "unconnected-(IC13A-R1OUT-Pad12)") (class "Default")
      (node (ref "IC13") (pin "12") (pinfunction "R1OUT_12") (pintype "output"))
    )
    (net (code "92") (name "unconnected-(IC13A-T1IN-Pad11)") (class "Default")
      (node (ref "IC13") (pin "11") (pinfunction "T1IN_11") (pintype "input"))
    )
    (net (code "93") (name "unconnected-(IC13A-T1OUT-Pad14)") (class "Default")
      (node (ref "IC13") (pin "14") (pinfunction "T1OUT_14") (pintype "output"))
    )
    (net (code "94") (name "unconnected-(TVS1-IO1-Pad1)") (class "Default")
      (node (ref "TVS1") (pin "1") (pinfunction "IO1_1") (pintype "bidirectional"))
    )
    (net (code "95") (name "unconnected-(TVS1-IO2-Pad3)") (class "Default")
      (node (ref "TVS1") (pin "3") (pinfunction "IO2_3") (pintype "bidirectional"))
    )
    (net (code "96") (name "unconnected-(U$2-PA6-PadP$22)") (class "Default")
      (node (ref "U$2") (pin "P$22") (pinfunction "PA6_P$22") (pintype "bidirectional"))
    )
    (net (code "97") (name "unconnected-(U$2-PA8-PadP$41)") (class "Default")
      (node (ref "U$2") (pin "P$41") (pinfunction "PA8_P$41") (pintype "bidirectional"))
    )
    (net (code "98") (name "unconnected-(U$2-PA12-PadP$45)") (class "Default")
      (node (ref "U$2") (pin "P$45") (pinfunction "PA12_P$45") (pintype "bidirectional"))
    )
    (net (code "99") (name "unconnected-(U$2-PB1-PadP$27)") (class "Default")
      (node (ref "U$2") (pin "P$27") (pinfunction "PB1_P$27") (pintype "bidirectional"))
    )
    (net (code "100") (name "unconnected-(U$2-PB2-PadP$28)") (class "Default")
      (node (ref "U$2") (pin "P$28") (pinfunction "PB2_P$28") (pintype "bidirectional"))
    )
    (net (code "101") (name "unconnected-(U$2-PB8-PadP$61)") (class "Default")
      (node (ref "U$2") (pin "P$61") (pinfunction "PB8_P$61") (pintype "bidirectional"))
    )
    (net (code "102") (name "unconnected-(U$2-PB9-PadP$62)") (class "Default")
      (node (ref "U$2") (pin "P$62") (pinfunction "PB9_P$62") (pintype "bidirectional"))
    )
    (net (code "103") (name "unconnected-(U$2-PB10-PadP$29)") (class "Default")
      (node (ref "U$2") (pin "P$29") (pinfunction "PB10_P$29") (pintype "bidirectional"))
    )
    (net (code "104") (name "unconnected-(U$2-PB12-PadP$33)") (class "Default")
      (node (ref "U$2") (pin "P$33") (pinfunction "PB12_P$33") (pintype "bidirectional"))
    )
    (net (code "105") (name "unconnected-(U$2-PB13-PadP$34)") (class "Default")
      (node (ref "U$2") (pin "P$34") (pinfunction "PB13_P$34") (pintype "bidirectional"))
    )
    (net (code "106") (name "unconnected-(U$2-PB14-PadP$35)") (class "Default")
      (node (ref "U$2") (pin "P$35") (pinfunction "PB14_P$35") (pintype "bidirectional"))
    )
    (net (code "107") (name "unconnected-(U$2-PC3-PadP$11)") (class "Default")
      (node (ref "U$2") (pin "P$11") (pinfunction "PC3_P$11") (pintype "bidirectional"))
    )
    (net (code "108") (name "unconnected-(U$2-PC5-PadP$25)") (class "Default")
      (node (ref "U$2") (pin "P$25") (pinfunction "PC5_P$25") (pintype "bidirectional"))
    )
    (net (code "109") (name "unconnected-(U$2-PC8-PadP$39)") (class "Default")
      (node (ref "U$2") (pin "P$39") (pinfunction "PC8_P$39") (pintype "bidirectional"))
    )
    (net (code "110") (name "unconnected-(U$2-PC9-PadP$40)") (class "Default")
      (node (ref "U$2") (pin "P$40") (pinfunction "PC9_P$40") (pintype "bidirectional"))
    )
    (net (code "111") (name "unconnected-(U$2-PC10-PadP$51)") (class "Default")
      (node (ref "U$2") (pin "P$51") (pinfunction "PC10_P$51") (pintype "bidirectional"))
    )
    (net (code "112") (name "unconnected-(U$2-PC11-PadP$52)") (class "Default")
      (node (ref "U$2") (pin "P$52") (pinfunction "PC11_P$52") (pintype "bidirectional"))
    )
    (net (code "113") (name "unconnected-(U$2-PC12-PadP$53)") (class "Default")
      (node (ref "U$2") (pin "P$53") (pinfunction "PC12_P$53") (pintype "bidirectional"))
    )
    (net (code "114") (name "unconnected-(U$2-PC13-PadP$2)") (class "Default")
      (node (ref "U$2") (pin "P$2") (pinfunction "PC13_P$2") (pintype "bidirectional"))
    )
    (net (code "115") (name "unconnected-(U$2-PC14-OSC32_ıN-PadP$3)") (class "Default")
      (node (ref "U$2") (pin "P$3") (pinfunction "PC14-OSC32_ıN_P$3") (pintype "bidirectional"))
    )
    (net (code "116") (name "unconnected-(U$2-PC15-OSC32_OUT-PadP$4)") (class "Default")
      (node (ref "U$2") (pin "P$4") (pinfunction "PC15-OSC32_OUT_P$4") (pintype "bidirectional"))
    )
    (net (code "117") (name "unconnected-(U$2-PD2-PadP$54)") (class "Default")
      (node (ref "U$2") (pin "P$54") (pinfunction "PD2_P$54") (pintype "bidirectional"))
    )
    (net (code "118") (name "unconnected-(U$2-PF0-OSC_ıN-PadP$5)") (class "Default")
      (node (ref "U$2") (pin "P$5") (pinfunction "PF0-OSC_ıN_P$5") (pintype "bidirectional"))
    )
    (net (code "119") (name "unconnected-(U$2-PF1-OSC_OUT-PadP$6)") (class "Default")
      (node (ref "U$2") (pin "P$6") (pinfunction "PF1-OSC_OUT_P$6") (pintype "bidirectional"))
    )
    (net (code "120") (name "unconnected-(U$3-N.C.-PadP$1)") (class "Default")
      (node (ref "U$3") (pin "P$1") (pinfunction "N.C._P$1") (pintype "bidirectional"))
    )
    (net (code "121") (name "unconnected-(U$12-CTS-Pad18)") (class "Default")
      (node (ref "U$12") (pin "18") (pinfunction "CTS_18") (pintype "bidirectional"))
    )
    (net (code "122") (name "unconnected-(U$12-DCD-Pad24)") (class "Default")
      (node (ref "U$12") (pin "24") (pinfunction "DCD_24") (pintype "bidirectional"))
    )
    (net (code "123") (name "unconnected-(U$12-DSR-Pad22)") (class "Default")
      (node (ref "U$12") (pin "22") (pinfunction "DSR_22") (pintype "bidirectional"))
    )
    (net (code "124") (name "unconnected-(U$12-DTR-Pad23)") (class "Default")
      (node (ref "U$12") (pin "23") (pinfunction "DTR_23") (pintype "bidirectional"))
    )
    (net (code "125") (name "unconnected-(U$12-GPIO.0-Pad14)") (class "Default")
      (node (ref "U$12") (pin "14") (pinfunction "GPIO.0_14") (pintype "bidirectional"))
    )
    (net (code "126") (name "unconnected-(U$12-GPIO.1-Pad13)") (class "Default")
      (node (ref "U$12") (pin "13") (pinfunction "GPIO.1_13") (pintype "bidirectional"))
    )
    (net (code "127") (name "unconnected-(U$12-GPIO.2-Pad12)") (class "Default")
      (node (ref "U$12") (pin "12") (pinfunction "GPIO.2_12") (pintype "bidirectional"))
    )
    (net (code "128") (name "unconnected-(U$12-GPIO.3-Pad11)") (class "Default")
      (node (ref "U$12") (pin "11") (pinfunction "GPIO.3_11") (pintype "bidirectional"))
    )
    (net (code "129") (name "unconnected-(U$12-NC-Pad10)") (class "Default")
      (node (ref "U$12") (pin "10") (pinfunction "NC_10") (pintype "bidirectional"))
    )
    (net (code "130") (name "unconnected-(U$12-RI-Pad1)") (class "Default")
      (node (ref "U$12") (pin "1") (pinfunction "RI_1") (pintype "bidirectional"))
    )
    (net (code "131") (name "unconnected-(U$12-RST-Pad9)") (class "Default")
      (node (ref "U$12") (pin "9") (pinfunction "RST_9") (pintype "bidirectional"))
    )
    (net (code "132") (name "unconnected-(U$12-RTS-Pad19)") (class "Default")
      (node (ref "U$12") (pin "19") (pinfunction "RTS_19") (pintype "bidirectional"))
    )
    (net (code "133") (name "unconnected-(U$12-SUSPEND-Pad15)") (class "Default")
      (node (ref "U$12") (pin "15") (pinfunction "SUSPEND_15") (pintype "bidirectional"))
    )
    (net (code "134") (name "unconnected-(U$12-SUSPEND1-Pad17)") (class "Default")
      (node (ref "U$12") (pin "17") (pinfunction "SUSPEND1_17") (pintype "bidirectional"))
    )
  )
)
